# blimp_v1.net
KiCad netlist of a schematic drawn in EAGLE
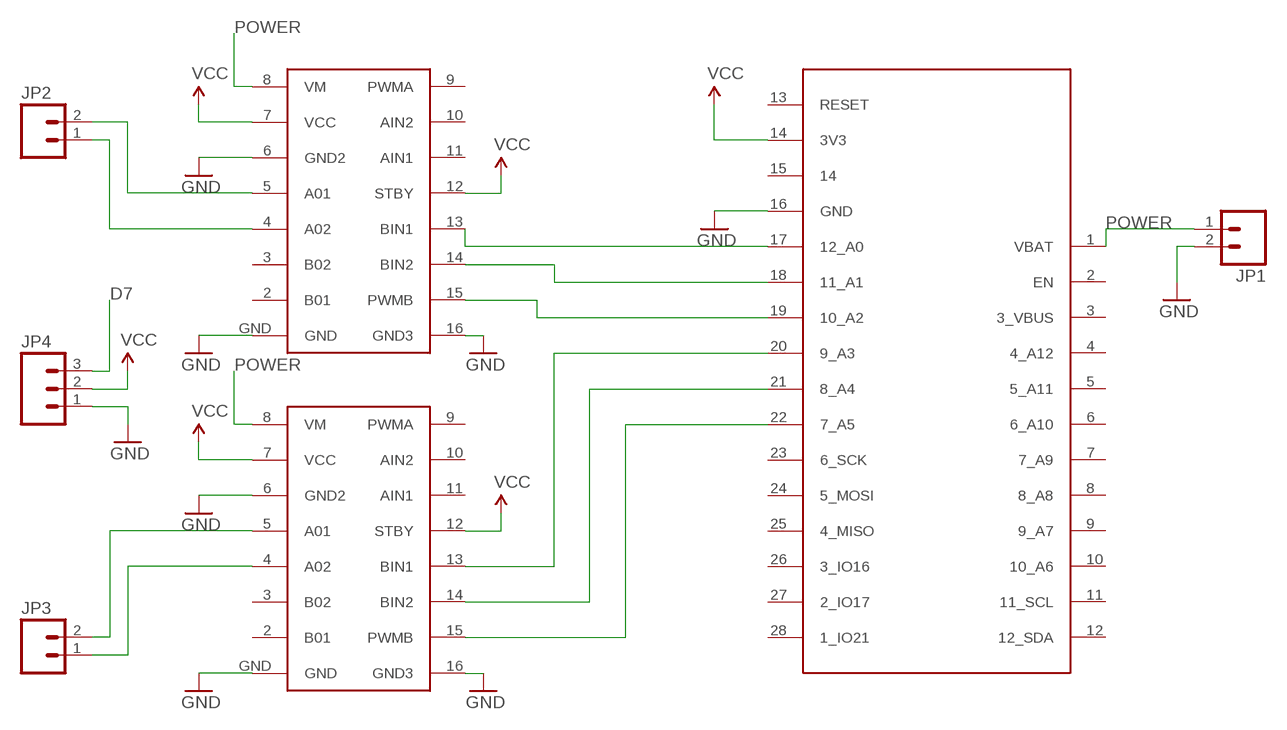
[diagram p0: schematic, sheet 1]

(export (version "E")
  (design (tool "Eeschema 10.0.6"))
  (components
    (comp (ref "JP1")
      (value "M02-JST-2MM-SMT")
      (footprint "eagle-import:JST-2-SMD")
      (libsource (lib "eagle-import") (part "M02-JST-2MM-SMT"))
    )
    (comp (ref "JP2")
      (value "M02PTH")
      (footprint "eagle-import:1X02")
      (libsource (lib "eagle-import") (part "M02PTH"))
    )
    (comp (ref "JP3")
      (value "M02PTH")
      (footprint "eagle-import:1X02")
      (libsource (lib "eagle-import") (part "M02PTH"))
    )
    (comp (ref "JP4")
      (value "M03PTH")
      (footprint "eagle-import:1X03")
      (libsource (lib "eagle-import") (part "M03PTH"))
    )
    (comp (ref "U$1")
      (value "ESP32")
      (footprint "eagle-import:ESP32")
      (libsource (lib "eagle-import") (part "ESP32"))
    )
    (comp (ref "U$2")
      (value "TB6612")
      (footprint "eagle-import:TB6612")
      (libsource (lib "eagle-import") (part "TB6612"))
    )
    (comp (ref "U$4")
      (value "TB6612")
      (footprint "eagle-import:TB6612")
      (libsource (lib "eagle-import") (part "TB6612"))
    )
  )
  (nets
    (net (code "1") (name "/D7") (class "Default")
      (node (ref "JP4") (pin "3") (pinfunction "3_3") (pintype "passive"))
    )
    (net (code "2") (name "/POWER") (class "Default")
      (node (ref "JP1") (pin "1") (pinfunction "1_1") (pintype "passive"))
      (node (ref "U$1") (pin "1") (pinfunction "VBAT_1") (pintype "bidirectional"))
      (node (ref "U$2") (pin "8") (pinfunction "VM_8") (pintype "bidirectional"))
      (node (ref "U$4") (pin "8") (pinfunction "VM_8") (pintype "bidirectional"))
    )
    (net (code "3") (name "GND") (class "Default")
      (node (ref "JP1") (pin "2") (pinfunction "2_2") (pintype "passive"))
      (node (ref "JP4") (pin "1") (pinfunction "1_1") (pintype "passive"))
      (node (ref "U$1") (pin "16") (pinfunction "GND_16") (pintype "bidirectional"))
      (node (ref "U$2") (pin "16") (pinfunction "GND3_16") (pintype "bidirectional"))
      (node (ref "U$2") (pin "6") (pinfunction "GND2_6") (pintype "bidirectional"))
      (node (ref "U$2") (pin "GND") (pinfunction "GND_GND") (pintype "bidirectional"))
      (node (ref "U$4") (pin "16") (pinfunction "GND3_16") (pintype "bidirectional"))
      (node (ref "U$4") (pin "6") (pinfunction "GND2_6") (pintype "bidirectional"))
      (node (ref "U$4") (pin "GND") (pinfunction "GND_GND") (pintype "bidirectional"))
    )
    (net (code "4") (name "Net-(U$1-7_A5)") (class "Default")
      (node (ref "U$1") (pin "22") (pinfunction "7_A5_22") (pintype "bidirectional"))
      (node (ref "U$2") (pin "15") (pinfunction "PWMB_15") (pintype "bidirectional"))
    )
    (net (code "5") (name "Net-(U$1-8_A4)") (class "Default")
      (node (ref "U$1") (pin "21") (pinfunction "8_A4_21") (pintype "bidirectional"))
      (node (ref "U$2") (pin "14") (pinfunction "BIN2_14") (pintype "bidirectional"))
    )
    (net (code "6") (name "Net-(U$1-9_A3)") (class "Default")
      (node (ref "U$1") (pin "20") (pinfunction "9_A3_20") (pintype "bidirectional"))
      (node (ref "U$2") (pin "13") (pinfunction "BIN1_13") (pintype "bidirectional"))
    )
    (net (code "7") (name "Net-(U$1-10_A2)") (class "Default")
      (node (ref "U$1") (pin "19") (pinfunction "10_A2_19") (pintype "bidirectional"))
      (node (ref "U$4") (pin "15") (pinfunction "PWMB_15") (pintype "bidirectional"))
    )
    (net (code "8") (name "Net-(U$1-11_A1)") (class "Default")
      (node (ref "U$1") (pin "18") (pinfunction "11_A1_18") (pintype "bidirectional"))
      (node (ref "U$4") (pin "14") (pinfunction "BIN2_14") (pintype "bidirectional"))
    )
    (net (code "9") (name "Net-(U$1-12_A0)") (class "Default")
      (node (ref "U$1") (pin "17") (pinfunction "12_A0_17") (pintype "bidirectional"))
      (node (ref "U$4") (pin "13") (pinfunction "BIN1_13") (pintype "bidirectional"))
    )
    (net (code "10") (name "Net-(U$2-A01)") (class "Default")
      (node (ref "JP3") (pin "2") (pinfunction "2_2") (pintype "passive"))
      (node (ref "U$2") (pin "5") (pinfunction "A01_5") (pintype "bidirectional"))
    )
    (net (code "11") (name "Net-(U$2-A02)") (class "Default")
      (node (ref "JP3") (pin "1") (pinfunction "1_1") (pintype "passive"))
      (node (ref "U$2") (pin "4") (pinfunction "A02_4") (pintype "bidirectional"))
    )
    (net (code "12") (name "Net-(U$4-A01)") (class "Default")
      (node (ref "JP2") (pin "2") (pinfunction "2_2") (pintype "passive"))
      (node (ref "U$4") (pin "5") (pinfunction "A01_5") (pintype "bidirectional"))
    )
    (net (code "13") (name "Net-(U$4-A02)") (class "Default")
      (node (ref "JP2") (pin "1") (pinfunction "1_1") (pintype "passive"))
      (node (ref "U$4") (pin "4") (pinfunction "A02_4") (pintype "bidirectional"))
    )
    (net (code "14") (name "VCC") (class "Default")
      (node (ref "JP4") (pin "2") (pinfunction "2_2") (pintype "passive"))
      (node (ref "U$1") (pin "14") (pinfunction "3V3_14") (pintype "bidirectional"))
      (node (ref "U$2") (pin "12") (pinfunction "STBY_12") (pintype "bidirectional"))
      (node (ref "U$2") (pin "7") (pinfunction "VCC_7") (pintype "bidirectional"))
      (node (ref "U$4") (pin "12") (pinfunction "STBY_12") (pintype "bidirectional"))
      (node (ref "U$4") (pin "7") (pinfunction "VCC_7") (pintype "bidirectional"))
    )
    (net (code "15") (name "unconnected-(U$1-1_IO21-Pad28)") (class "Default")
      (node (ref "U$1") (pin "28") (pinfunction "1_IO21_28") (pintype "bidirectional"))
    )
    (net (code "16") (name "unconnected-(U$1-2_IO17-Pad27)") (class "Default")
      (node (ref "U$1") (pin "27") (pinfunction "2_IO17_27") (pintype "bidirectional"))
    )
    (net (code "17") (name "unconnected-(U$1-3_IO16-Pad26)") (class "Default")
      (node (ref "U$1") (pin "26") (pinfunction "3_IO16_26") (pintype "bidirectional"))
    )
    (net (code "18") (name "unconnected-(U$1-3_VBUS-Pad3)") (class "Default")
      (node (ref "U$1") (pin "3") (pinfunction "3_VBUS_3") (pintype "bidirectional"))
    )
    (net (code "19") (name "unconnected-(U$1-4_A12-Pad4)") (class "Default")
      (node (ref "U$1") (pin "4") (pinfunction "4_A12_4") (pintype "bidirectional"))
    )
    (net (code "20") (name "unconnected-(U$1-4_MISO-Pad25)") (class "Default")
      (node (ref "U$1") (pin "25") (pinfunction "4_MISO_25") (pintype "bidirectional"))
    )
    (net (code "21") (name "unconnected-(U$1-5_A11-Pad5)") (class "Default")
      (node (ref "U$1") (pin "5") (pinfunction "5_A11_5") (pintype "bidirectional"))
    )
    (net (code "22") (name "unconnected-(U$1-5_MOSI-Pad24)") (class "Default")
      (node (ref "U$1") (pin "24") (pinfunction "5_MOSI_24") (pintype "bidirectional"))
    )
    (net (code "23") (name "unconnected-(U$1-6_A10-Pad6)") (class "Default")
      (node (ref "U$1") (pin "6") (pinfunction "6_A10_6") (pintype "bidirectional"))
    )
    (net (code "24") (name "unconnected-(U$1-6_SCK-Pad23)") (class "Default")
      (node (ref "U$1") (pin "23") (pinfunction "6_SCK_23") (pintype "bidirectional"))
    )
    (net (code "25") (name "unconnected-(U$1-7_A9-Pad7)") (class "Default")
      (node (ref "U$1") (pin "7") (pinfunction "7_A9_7") (pintype "bidirectional"))
    )
    (net (code "26") (name "unconnected-(U$1-8_A8-Pad8)") (class "Default")
      (node (ref "U$1") (pin "8") (pinfunction "8_A8_8") (pintype "bidirectional"))
    )
    (net (code "27") (name "unconnected-(U$1-9_A7-Pad9)") (class "Default")
      (node (ref "U$1") (pin "9") (pinfunction "9_A7_9") (pintype "bidirectional"))
    )
    (net (code "28") (name "unconnected-(U$1-10_A6-Pad10)") (class "Default")
      (node (ref "U$1") (pin "10") (pinfunction "10_A6_10") (pintype "bidirectional"))
    )
    (net (code "29") (name "unconnected-(U$1-11_SCL-Pad11)") (class "Default")
      (node (ref "U$1") (pin "11") (pinfunction "11_SCL_11") (pintype "bidirectional"))
    )
    (net (code "30") (name "unconnected-(U$1-12_SDA-Pad12)") (class "Default")
      (node (ref "U$1") (pin "12") (pinfunction "12_SDA_12") (pintype "bidirectional"))
    )
    (net (code "31") (name "unconnected-(U$1-14-Pad15)") (class "Default")
      (node (ref "U$1") (pin "15") (pinfunction "14_15") (pintype "bidirectional"))
    )
    (net (code "32") (name "unconnected-(U$1-EN-Pad2)") (class "Default")
      (node (ref "U$1") (pin "2") (pinfunction "EN_2") (pintype "bidirectional"))
    )
    (net (code "33") (name "unconnected-(U$1-RESET-Pad13)") (class "Default")
      (node (ref "U$1") (pin "13") (pinfunction "RESET_13") (pintype "bidirectional"))
    )
    (net (code "34") (name "unconnected-(U$2-AIN1-Pad11)") (class "Default")
      (node (ref "U$2") (pin "11") (pinfunction "AIN1_11") (pintype "bidirectional"))
    )
    (net (code "35") (name "unconnected-(U$2-AIN2-Pad10)") (class "Default")
      (node (ref "U$2") (pin "10") (pinfunction "AIN2_10") (pintype "bidirectional"))
    )
    (net (code "36") (name "unconnected-(U$2-B01-Pad2)") (class "Default")
      (node (ref "U$2") (pin "2") (pinfunction "B01_2") (pintype "bidirectional"))
    )
    (net (code "37") (name "unconnected-(U$2-B02-Pad3)") (class "Default")
      (node (ref "U$2") (pin "3") (pinfunction "B02_3") (pintype "bidirectional"))
    )
    (net (code "38") (name "unconnected-(U$2-PWMA-Pad9)") (class "Default")
      (node (ref "U$2") (pin "9") (pinfunction "PWMA_9") (pintype "bidirectional"))
    )
    (net (code "39") (name "unconnected-(U$4-AIN1-Pad11)") (class "Default")
      (node (ref "U$4") (pin "11") (pinfunction "AIN1_11") (pintype "bidirectional"))
    )
    (net (code "40") (name "unconnected-(U$4-AIN2-Pad10)") (class "Default")
      (node (ref "U$4") (pin "10") (pinfunction "AIN2_10") (pintype "bidirectional"))
    )
    (net (code "41") (name "unconnected-(U$4-B01-Pad2)") (class "Default")
      (node (ref "U$4") (pin "2") (pinfunction "B01_2") (pintype "bidirectional"))
    )
    (net (code "42") (name "unconnected-(U$4-B02-Pad3)") (class "Default")
      (node (ref "U$4") (pin "3") (pinfunction "B02_3") (pintype "bidirectional"))
    )
    (net (code "43") (name "unconnected-(U$4-PWMA-Pad9)") (class "Default")
      (node (ref "U$4") (pin "9") (pinfunction "PWMA_9") (pintype "bidirectional"))
    )
  )
)
